# Power.net
KiCad netlist of a schematic drawn in Altium Designer
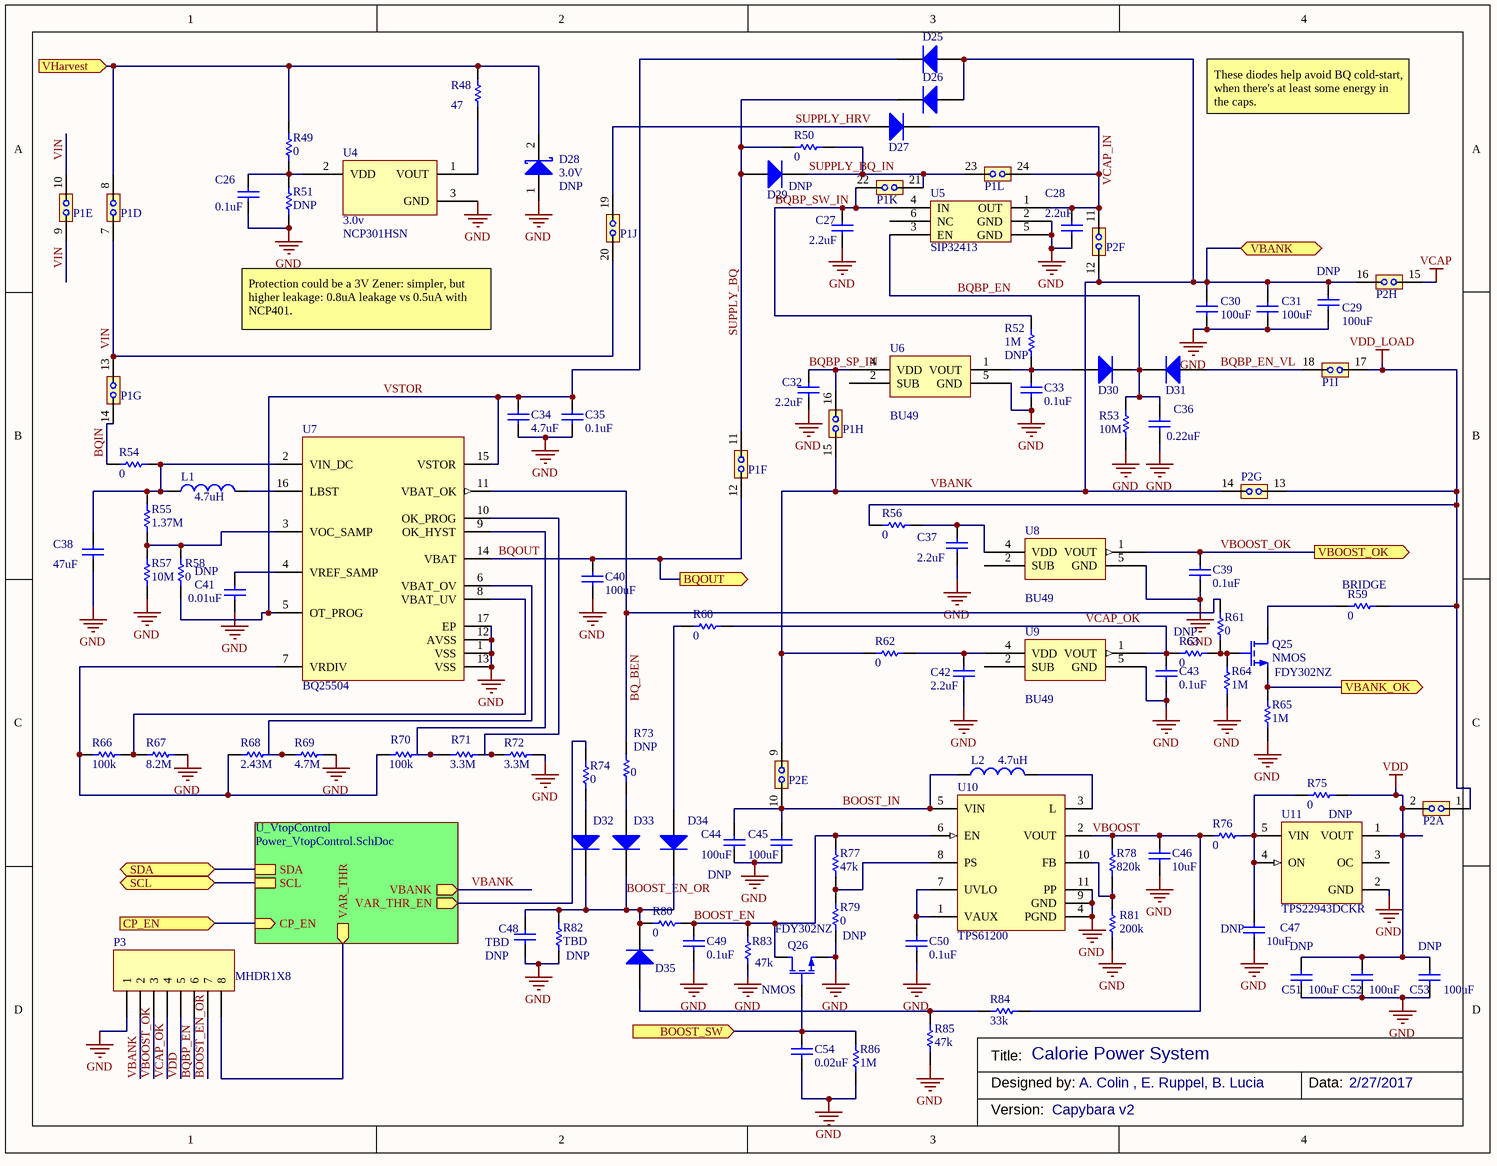
[diagram p0: Power.SchDoc]

(export (version "E")
  (design (tool "Eeschema 10.0.6"))
  (components
    (comp (ref "C26")
      (value "0.1uF")
      (footprint "0603")
      (description "Ceramic Capacitor (Surface Mount)")
      (fields
        (field (name "MANUFACTURER") "Murata Electronics North America")
        (field (name "MANUFACTURER PART NUMBER") "GRM188R71C104KA01D")
      )
      (libsource (lib "DRP_Basic_2014") (part "Cap"))
    )
    (comp (ref "C27")
      (value "2.2uF")
      (footprint "0603")
      (description "Ceramic Capacitor (Surface Mount)")
      (fields
        (field (name "MANUFACTURER") "Murata Electronics North America")
        (field (name "MANUFACTURER PART NUMBER") "GRM188R61C225KE15D")
      )
      (libsource (lib "DRP_Basic_2014") (part "Cap"))
    )
    (comp (ref "C28")
      (value "2.2uF")
      (footprint "0603")
      (description "Ceramic Capacitor (Surface Mount)")
      (fields
        (field (name "MANUFACTURER") "Murata Electronics North America")
        (field (name "MANUFACTURER PART NUMBER") "GRM188R61C225KE15D")
      )
      (libsource (lib "DRP_Basic_2014") (part "Cap"))
    )
    (comp (ref "C29")
      (value "100uF")
      (footprint "0805")
      (description "Ceramic Capacitor (Surface Mount)")
      (fields
        (field (name "MANUFACTURER") "Murata Electronics North America")
        (field (name "MANUFACTURER PART NUMBER") "GRM21BR60J107ME15L")
        (field (name "NOTE") "DNP")
      )
      (libsource (lib "DRP_Basic_2014") (part "Cap"))
    )
    (comp (ref "C30")
      (value "100uF")
      (footprint "0805")
      (description "Ceramic Capacitor (Surface Mount)")
      (fields
        (field (name "MANUFACTURER") "Murata Electronics North America")
        (field (name "MANUFACTURER PART NUMBER") "GRM21BR60G107ME15L")
      )
      (libsource (lib "DRP_Basic_2014") (part "Cap"))
    )
    (comp (ref "C31")
      (value "100uF")
      (footprint "0805")
      (description "Ceramic Capacitor (Surface Mount)")
      (fields
        (field (name "MANUFACTURER") "Murata Electronics North America")
        (field (name "MANUFACTURER PART NUMBER") "GRM21BR60G107ME15L")
      )
      (libsource (lib "DRP_Basic_2014") (part "Cap"))
    )
    (comp (ref "C32")
      (value "2.2uF")
      (footprint "0603")
      (description "Ceramic Capacitor (Surface Mount)")
      (fields
        (field (name "MANUFACTURER") "Murata Electronics North America")
        (field (name "MANUFACTURER PART NUMBER") "GRM188R61C225KE15D")
      )
      (libsource (lib "DRP_Basic_2014") (part "Cap"))
    )
    (comp (ref "C33")
      (value "0.1uF")
      (footprint "0603")
      (description "Ceramic Capacitor (Surface Mount)")
      (fields
        (field (name "MANUFACTURER") "Murata Electronics North America")
        (field (name "MANUFACTURER PART NUMBER") "GRM188R71C104KA01D")
      )
      (libsource (lib "DRP_Basic_2014") (part "Cap"))
    )
    (comp (ref "C34")
      (value "4.7uF")
      (footprint "0603")
      (description "Ceramic Capacitor (Surface Mount)")
      (fields
        (field (name "MANUFACTURER") "Samsung Electro-Mechanics")
        (field (name "MANUFACTURER PART NUMBER") "CL10B475KQ8NQNC")
      )
      (libsource (lib "DRP_Basic_2014") (part "Cap"))
    )
    (comp (ref "C35")
      (value "0.1uF")
      (footprint "0603")
      (description "Ceramic Capacitor (Surface Mount)")
      (fields
        (field (name "MANUFACTURER") "Murata Electronics North America")
        (field (name "MANUFACTURER PART NUMBER") "GRM188R71C104KA01D")
      )
      (libsource (lib "DRP_Basic_2014") (part "Cap"))
    )
    (comp (ref "C36")
      (value "0.22uF")
      (footprint "0603")
      (description "Ceramic Capacitor (Surface Mount)")
      (fields
        (field (name "MANUFACTURER") "Murata Electronics North America")
        (field (name "MANUFACTURER PART NUMBER") "GRM188R71E224KA88D")
      )
      (libsource (lib "DRP_Basic_2014") (part "Cap"))
    )
    (comp (ref "C37")
      (value "2.2uF")
      (footprint "0603")
      (description "Ceramic Capacitor (Surface Mount)")
      (fields
        (field (name "MANUFACTURER") "Murata Electronics North America")
        (field (name "MANUFACTURER PART NUMBER") "GRM188R61C225KE15D")
      )
      (libsource (lib "DRP_Basic_2014") (part "Cap"))
    )
    (comp (ref "C38")
      (value "47uF")
      (footprint "0603")
      (description "Ceramic Capacitor (Surface Mount)")
      (fields
        (field (name "MANUFACTURER") "Samsung Electro-Mechanics")
        (field (name "MANUFACTURER PART NUMBER") "CL10A476MR8NZNE")
      )
      (libsource (lib "DRP_Basic_2014") (part "Cap"))
    )
    (comp (ref "C39")
      (value "0.1uF")
      (footprint "0603")
      (description "Ceramic Capacitor (Surface Mount)")
      (fields
        (field (name "MANUFACTURER") "Murata Electronics North America")
        (field (name "MANUFACTURER PART NUMBER") "GRM188R71C104KA01D")
      )
      (libsource (lib "DRP_Basic_2014") (part "Cap"))
    )
    (comp (ref "C40")
      (value "100uF")
      (footprint "0805")
      (description "Ceramic Capacitor (Surface Mount)")
      (fields
        (field (name "MANUFACTURER") "Murata Electronics North America")
        (field (name "MANUFACTURER PART NUMBER") "GRM21BR60G107ME15L")
      )
      (libsource (lib "DRP_Basic_2014") (part "Cap"))
    )
    (comp (ref "C41")
      (value "0.01uF")
      (footprint "0603")
      (description "Ceramic Capacitor (Surface Mount)")
      (fields
        (field (name "MANUFACTURER") "Murata Electronics North America")
        (field (name "MANUFACTURER PART NUMBER") "GRM155R71E103JA01J")
      )
      (libsource (lib "DRP_Basic_2014") (part "Cap"))
    )
    (comp (ref "C42")
      (value "2.2uF")
      (footprint "0603")
      (description "Ceramic Capacitor (Surface Mount)")
      (fields
        (field (name "MANUFACTURER") "Murata Electronics North America")
        (field (name "MANUFACTURER PART NUMBER") "GRM188R61C225KE15D")
      )
      (libsource (lib "DRP_Basic_2014") (part "Cap"))
    )
    (comp (ref "C43")
      (value "0.1uF")
      (footprint "0603")
      (description "Ceramic Capacitor (Surface Mount)")
      (fields
        (field (name "MANUFACTURER") "Murata Electronics North America")
        (field (name "MANUFACTURER PART NUMBER") "GRM188R71C104KA01D")
      )
      (libsource (lib "DRP_Basic_2014") (part "Cap"))
    )
    (comp (ref "C44")
      (value "100uF")
      (footprint "0805")
      (description "Ceramic Capacitor (Surface Mount)")
      (fields
        (field (name "MANUFACTURER") "Murata Electronics North America")
        (field (name "MANUFACTURER PART NUMBER") "GRM21BR60G107ME15L")
        (field (name "NOTE") "DNP")
      )
      (libsource (lib "DRP_Basic_2014") (part "Cap"))
    )
    (comp (ref "C45")
      (value "100uF")
      (footprint "0805")
      (description "Ceramic Capacitor (Surface Mount)")
      (fields
        (field (name "MANUFACTURER") "Murata Electronics North America")
        (field (name "MANUFACTURER PART NUMBER") "GRM21BR60G107ME15L")
      )
      (libsource (lib "DRP_Basic_2014") (part "Cap"))
    )
    (comp (ref "C46")
      (value "10uF")
      (footprint "0603")
      (description "Ceramic Capacitor (Surface Mount)")
      (fields
        (field (name "MANUFACTURER") "Murata Electronics North America")
        (field (name "MANUFACTURER PART NUMBER") "GRM188R60J106ME47D")
      )
      (libsource (lib "DRP_Basic_2014") (part "Cap"))
    )
    (comp (ref "C47")
      (value "10uF")
      (footprint "0805")
      (description "Ceramic Capacitor (Surface Mount)")
      (fields
        (field (name "MANUFACTURER") "Murata Electronics North America")
        (field (name "MANUFACTURER PART NUMBER") "GRM21BR61E106MA73L")
        (field (name "NOTE") "DNP")
      )
      (libsource (lib "DRP_Basic_2014") (part "Cap"))
    )
    (comp (ref "C48")
      (value "TBD")
      (footprint "0603")
      (description "Ceramic Capacitor (Surface Mount)")
      (fields
        (field (name "MANUFACTURER") "Generic Ceramic Chip Cap (TBD)")
        (field (name "NOTE") "DNP")
        (field (name "Comment") "Cap")
      )
      (libsource (lib "DRP_Basic_2014") (part "Cap"))
    )
    (comp (ref "C49")
      (value "0.1uF")
      (footprint "0603")
      (description "Ceramic Capacitor (Surface Mount)")
      (fields
        (field (name "MANUFACTURER") "Murata Electronics North America")
        (field (name "MANUFACTURER PART NUMBER") "GRM188R71C104KA01D")
      )
      (libsource (lib "DRP_Basic_2014") (part "Cap"))
    )
    (comp (ref "C50")
      (value "0.1uF")
      (footprint "0603")
      (description "Ceramic Capacitor (Surface Mount)")
      (fields
        (field (name "MANUFACTURER") "Murata Electronics North America")
        (field (name "MANUFACTURER PART NUMBER") "GRM188R71C104KA01D")
      )
      (libsource (lib "DRP_Basic_2014") (part "Cap"))
    )
    (comp (ref "C51")
      (value "100uF")
      (footprint "0805")
      (description "Ceramic Capacitor (Surface Mount)")
      (fields
        (field (name "MANUFACTURER") "Murata Electronics North America")
        (field (name "MANUFACTURER PART NUMBER") "GRM21BR60G107ME15L")
        (field (name "NOTE") "DNP")
      )
      (libsource (lib "DRP_Basic_2014") (part "Cap"))
    )
    (comp (ref "C52")
      (value "100uF")
      (footprint "0805")
      (description "Ceramic Capacitor (Surface Mount)")
      (fields
        (field (name "MANUFACTURER") "Murata Electronics North America")
        (field (name "MANUFACTURER PART NUMBER") "GRM21BR60G107ME15L")
      )
      (libsource (lib "DRP_Basic_2014") (part "Cap"))
    )
    (comp (ref "C53")
      (value "100uF")
      (footprint "0805")
      (description "Ceramic Capacitor (Surface Mount)")
      (fields
        (field (name "MANUFACTURER") "Murata Electronics North America")
        (field (name "MANUFACTURER PART NUMBER") "GRM21BR60G107ME15L")
        (field (name "NOTE") "DNP")
      )
      (libsource (lib "DRP_Basic_2014") (part "Cap"))
    )
    (comp (ref "C54")
      (value "0.02uF")
      (footprint "0603")
      (description "Ceramic Capacitor (Surface Mount)")
      (fields
        (field (name "MANUFACTURER") "Samsung Electro-Mechanics")
        (field (name "MANUFACTURER PART NUMBER") "CL10B203KB8NNNC")
      )
      (libsource (lib "DRP_Basic_2014") (part "Cap"))
    )
    (comp (ref "D25")
      (value "Diode")
      (footprint "SOD-523")
      (description "General Purpose Diode")
      (fields
        (field (name "MANUFACTURER") "Vishay Semiconductor")
        (field (name "MANUFACTURER PART NUMBER") "BAS40-02V-V-G-08")
      )
      (libsource (lib "DRP_Basic_2014") (part "Diode"))
    )
    (comp (ref "D26")
      (value "Diode")
      (footprint "SOD-523")
      (description "General Purpose Diode")
      (fields
        (field (name "MANUFACTURER") "Vishay Semiconductor")
        (field (name "MANUFACTURER PART NUMBER") "BAS40-02V-V-G-08")
      )
      (libsource (lib "DRP_Basic_2014") (part "Diode"))
    )
    (comp (ref "D27")
      (value "Diode")
      (footprint "SOD-523")
      (description "General Purpose Diode")
      (fields
        (field (name "MANUFACTURER") "Vishay Semiconductor")
        (field (name "MANUFACTURER PART NUMBER") "BAS40-02V-V-G-08")
      )
      (libsource (lib "DRP_Basic_2014") (part "Diode"))
    )
    (comp (ref "D28")
      (value "3.0V")
      (footprint "DIOD-SOD-123-2_V")
      (fields
        (field (name "MANUFACTURER PART NUMBER") "MMSZ4683-TP")
        (field (name "MANUFACTURER") "Micro Commercial Co")
        (field (name "NOTE") "DNP")
        (field (name "DIGI-KEY PART NUMBER") "MMSZ4683-TPMSCT-ND")
      )
      (libsource (lib "Altium Content Vault") (part "CMP-0303-00003-1"))
    )
    (comp (ref "D29")
      (value "Diode")
      (footprint "SOD-523")
      (description "General Purpose Diode")
      (fields
        (field (name "MANUFACTURER") "Vishay Semiconductor")
        (field (name "MANUFACTURER PART NUMBER") "BAS40-02V-V-G-08")
        (field (name "NOTE") "DNP")
      )
      (libsource (lib "DRP_Basic_2014") (part "Diode"))
    )
    (comp (ref "D30")
      (value "Diode")
      (footprint "SOD-523")
      (description "General Purpose Diode")
      (fields
        (field (name "MANUFACTURER") "Vishay Semiconductor")
        (field (name "MANUFACTURER PART NUMBER") "BAS40-02V-V-G-08")
      )
      (libsource (lib "DRP_Basic_2014") (part "Diode"))
    )
    (comp (ref "D31")
      (value "Diode")
      (footprint "SOD-523")
      (description "General Purpose Diode")
      (fields
        (field (name "MANUFACTURER") "Vishay Semiconductor")
        (field (name "MANUFACTURER PART NUMBER") "BAS40-02V-V-G-08")
      )
      (libsource (lib "DRP_Basic_2014") (part "Diode"))
    )
    (comp (ref "D32")
      (value "Diode")
      (footprint "SOD-523")
      (description "General Purpose Diode")
      (fields
        (field (name "MANUFACTURER") "Vishay Semiconductor")
        (field (name "MANUFACTURER PART NUMBER") "BAS40-02V-V-G-08")
      )
      (libsource (lib "DRP_Basic_2014") (part "Diode"))
    )
    (comp (ref "D33")
      (value "Diode")
      (footprint "SOD-523")
      (description "General Purpose Diode")
      (fields
        (field (name "MANUFACTURER") "Vishay Semiconductor")
        (field (name "MANUFACTURER PART NUMBER") "BAS40-02V-V-G-08")
      )
      (libsource (lib "DRP_Basic_2014") (part "Diode"))
    )
    (comp (ref "D34")
      (value "Diode")
      (footprint "SOD-523")
      (description "General Purpose Diode")
      (fields
        (field (name "MANUFACTURER") "Vishay Semiconductor")
        (field (name "MANUFACTURER PART NUMBER") "BAS40-02V-V-G-08")
      )
      (libsource (lib "DRP_Basic_2014") (part "Diode"))
    )
    (comp (ref "D35")
      (value "Diode")
      (footprint "SOD-523")
      (description "General Purpose Diode")
      (fields
        (field (name "MANUFACTURER") "Vishay Semiconductor")
        (field (name "MANUFACTURER PART NUMBER") "BAS40-02V-V-G-08")
      )
      (libsource (lib "DRP_Basic_2014") (part "Diode"))
    )
    (comp (ref "L1")
      (value "4.7uH")
      (footprint "PFL1609")
      (description "Inductor")
      (fields
        (field (name "DISTRIBUTOR PART NUMBER") "994-PFL1609-472MEU")
        (field (name "MANUFACTURER") "Coilcraft")
      )
      (libsource (lib "Miscellaneous Devices") (part "Inductor"))
    )
    (comp (ref "L2")
      (value "4.7uH")
      (footprint "PFL1609")
      (description "Inductor")
      (fields
        (field (name "DISTRIBUTOR PART NUMBER") "994-PFL1609-472MEU")
        (field (name "MANUFACTURER") "Coilcraft")
      )
      (libsource (lib "Miscellaneous Devices") (part "Inductor"))
    )
    (comp (ref "P1") (value "JMPHDR_12") (footprint "MHDR2X12") (libsource (lib "") (part "JMPHDR_12_4")))
    (comp (ref "P2")
      (value "JMPHDR_8")
      (fields
        (field (name "DIGI-KEY PART NUMBER") "S9015E-08-ND")
        (field (name "MANUFACTURER") "Sullins Connector Solutions")
        (field (name "MANUFACTURER PART NUMBER") "GRPB082VWVN-RC")
      )
      (libsource (lib "") (part "JMPHDR_8_3"))
    )
    (comp (ref "P3")
      (value "MHDR1X8")
      (footprint "MHDR1X8")
      (description "Header, 8-Pin")
      (fields
        (field (name "DIGI-KEY PART NUMBER") "952-3361-ND")
        (field (name "DISTRIBUTOR PART NUMBER") "855-M52-5000845")
        (field (name "PUBLISHER") "Altium Limited")
      )
      (libsource (lib "Miscellaneous Connectors") (part "MHDR1X8"))
    )
    (comp (ref "Q25")
      (value "NMOS")
      (footprint "SOT-523-3")
      (description "N-Channel MOSFET")
      (fields
        (field (name "MANUFACTURER PART NUMBER") "FDY302NZ")
        (field (name "MANUFACTURER") "Fairchild")
        (field (name "DISTRIBUTOR PART NUMBER") "FDY302NZCT-ND")
      )
      (libsource (lib "DRP_Basic_2014") (part "MOSFET-N"))
    )
    (comp (ref "Q26")
      (value "NMOS")
      (footprint "SOT-523-3")
      (description "N-Channel MOSFET")
      (fields
        (field (name "MANUFACTURER PART NUMBER") "FDY302NZ")
        (field (name "MANUFACTURER") "Fairchild")
        (field (name "DISTRIBUTOR PART NUMBER") "FDY302NZCT-ND")
      )
      (libsource (lib "DRP_Basic_2014") (part "MOSFET-N"))
    )
    (comp (ref "R48")
      (value "47")
      (footprint "0603")
      (description "Chip Resistor (Surface Mount)")
      (fields
        (field (name "MANUFACTURER") "Yageo")
        (field (name "MANUFACTURER PART NUMBER") "RC0603JR-0747RL")
      )
      (libsource (lib "DRP_Basic_2014") (part "Res"))
    )
    (comp (ref "R49")
      (value "0")
      (footprint "0603")
      (description "Chip Resistor (Surface Mount)")
      (fields
        (field (name "MANUFACTURER") "Yageo")
        (field (name "MANUFACTURER PART NUMBER") "RC0603JR-070RL")
      )
      (libsource (lib "DRP_Basic_2014") (part "Res"))
    )
    (comp (ref "R50")
      (value "0")
      (footprint "0603")
      (description "Chip Resistor (Surface Mount)")
      (fields
        (field (name "MANUFACTURER") "Yageo")
        (field (name "MANUFACTURER PART NUMBER") "RC0603JR-070RL")
      )
      (libsource (lib "DRP_Basic_2014") (part "Res"))
    )
    (comp (ref "R51")
      (value "DNP")
      (footprint "0603")
      (description "Chip Resistor (Surface Mount)")
      (fields (field (name "MANUFACTURER") "Yageo") (field (name "Comment") "Res"))
      (libsource (lib "DRP_Basic_2014") (part "Res"))
    )
    (comp (ref "R52")
      (value "1M")
      (footprint "0603")
      (description "Chip Resistor (Surface Mount)")
      (fields
        (field (name "MANUFACTURER") "Yageo")
        (field (name "MANUFACTURER PART NUMBER") "RC0603FR-071ML")
        (field (name "NOTE") "DNP")
      )
      (libsource (lib "DRP_Basic_2014") (part "Res"))
    )
    (comp (ref "R53")
      (value "10M")
      (footprint "0603")
      (description "Chip Resistor (Surface Mount)")
      (fields
        (field (name "MANUFACTURER") "Yageo")
        (field (name "MANUFACTURER PART NUMBER") "RC0603JR-0710ML")
      )
      (libsource (lib "DRP_Basic_2014") (part "Res"))
    )
    (comp (ref "R54")
      (value "0")
      (footprint "0603")
      (description "Chip Resistor (Surface Mount)")
      (fields
        (field (name "MANUFACTURER") "Yageo")
        (field (name "MANUFACTURER PART NUMBER") "RC0603JR-070RL")
      )
      (libsource (lib "DRP_Basic_2014") (part "Res"))
    )
    (comp (ref "R55")
      (value "1.37M")
      (footprint "0603")
      (description "Chip Resistor (Surface Mount)")
      (fields
        (field (name "MANUFACTURER") "Vishay Dale")
        (field (name "MANUFACTURER PART NUMBER") "CRCW04021M37FKED")
      )
      (libsource (lib "DRP_Basic_2014") (part "Res"))
    )
    (comp (ref "R56")
      (value "0")
      (footprint "0603")
      (description "Chip Resistor (Surface Mount)")
      (fields
        (field (name "MANUFACTURER") "Yageo")
        (field (name "MANUFACTURER PART NUMBER") "RC0603JR-070RL")
      )
      (libsource (lib "DRP_Basic_2014") (part "Res"))
    )
    (comp (ref "R57")
      (value "10M")
      (footprint "0603")
      (description "Chip Resistor (Surface Mount)")
      (fields
        (field (name "MANUFACTURER") "Yageo")
        (field (name "MANUFACTURER PART NUMBER") "RC0603JR-0710ML")
      )
      (libsource (lib "DRP_Basic_2014") (part "Res"))
    )
    (comp (ref "R58")
      (value "0")
      (footprint "0603")
      (description "Chip Resistor (Surface Mount)")
      (fields
        (field (name "MANUFACTURER") "Yageo")
        (field (name "MANUFACTURER PART NUMBER") "RC0603JR-070RL")
        (field (name "NOTE") "DNP")
      )
      (libsource (lib "DRP_Basic_2014") (part "Res"))
    )
    (comp (ref "R59")
      (value "0")
      (footprint "0603")
      (description "Chip Resistor (Surface Mount)")
      (fields
        (field (name "MANUFACTURER") "Yageo")
        (field (name "MANUFACTURER PART NUMBER") "RC0603JR-070RL")
        (field (name "NOTE") "BRIDGE")
      )
      (libsource (lib "DRP_Basic_2014") (part "Res"))
    )
    (comp (ref "R60")
      (value "0")
      (footprint "0603")
      (description "Chip Resistor (Surface Mount)")
      (fields
        (field (name "MANUFACTURER") "Yageo")
        (field (name "MANUFACTURER PART NUMBER") "RC0603JR-070RL")
      )
      (libsource (lib "DRP_Basic_2014") (part "Res"))
    )
    (comp (ref "R61")
      (value "0")
      (footprint "0603")
      (description "Chip Resistor (Surface Mount)")
      (fields
        (field (name "MANUFACTURER") "Yageo")
        (field (name "MANUFACTURER PART NUMBER") "RC0603JR-070RL")
      )
      (libsource (lib "DRP_Basic_2014") (part "Res"))
    )
    (comp (ref "R62")
      (value "0")
      (footprint "0603")
      (description "Chip Resistor (Surface Mount)")
      (fields
        (field (name "MANUFACTURER") "Yageo")
        (field (name "MANUFACTURER PART NUMBER") "RC0603JR-070RL")
      )
      (libsource (lib "DRP_Basic_2014") (part "Res"))
    )
    (comp (ref "R63")
      (value "0")
      (footprint "0603")
      (description "Chip Resistor (Surface Mount)")
      (fields
        (field (name "MANUFACTURER") "Yageo")
        (field (name "MANUFACTURER PART NUMBER") "RC0603JR-070RL")
        (field (name "NOTE") "DNP")
      )
      (libsource (lib "DRP_Basic_2014") (part "Res"))
    )
    (comp (ref "R64")
      (value "1M")
      (footprint "0603")
      (description "Chip Resistor (Surface Mount)")
      (fields
        (field (name "MANUFACTURER") "Yageo")
        (field (name "MANUFACTURER PART NUMBER") "RC0603FR-071ML")
      )
      (libsource (lib "DRP_Basic_2014") (part "Res"))
    )
    (comp (ref "R65")
      (value "1M")
      (footprint "0603")
      (description "Chip Resistor (Surface Mount)")
      (fields
        (field (name "MANUFACTURER") "Yageo")
        (field (name "MANUFACTURER PART NUMBER") "RC0603FR-071ML")
      )
      (libsource (lib "DRP_Basic_2014") (part "Res"))
    )
    (comp (ref "R66")
      (value "100k")
      (footprint "0603")
      (description "Chip Resistor (Surface Mount)")
      (fields
        (field (name "MANUFACTURER") "Yageo")
        (field (name "MANUFACTURER PART NUMBER") "RT0603FRE07100KL")
      )
      (libsource (lib "DRP_Basic_2014") (part "Res"))
    )
    (comp (ref "R67")
      (value "8.2M")
      (footprint "0603")
      (description "Chip Resistor (Surface Mount)")
      (fields
        (field (name "MANUFACTURER") "Vishay Dale")
        (field (name "MANUFACTURER PART NUMBER") "CRCW06038M20FKEA")
      )
      (libsource (lib "DRP_Basic_2014") (part "Res"))
    )
    (comp (ref "R68")
      (value "2.43M")
      (footprint "0603")
      (description "Chip Resistor (Surface Mount)")
      (fields
        (field (name "MANUFACTURER") "Vishay")
        (field (name "MANUFACTURER PART NUMBER") "CRCW06032M43FKEA")
      )
      (libsource (lib "DRP_Basic_2014") (part "Res"))
    )
    (comp (ref "R69")
      (value "4.7M")
      (footprint "0603")
      (description "Chip Resistor (Surface Mount)")
      (fields
        (field (name "MANUFACTURER") "Generic Chip Res (TBD)")
        (field (name "MANUFACTURER PART NUMBER") "RC0603FR-074M7L")
      )
      (libsource (lib "DRP_Basic_2014") (part "Res"))
    )
    (comp (ref "R70")
      (value "100k")
      (footprint "0603")
      (description "Chip Resistor (Surface Mount)")
      (fields
        (field (name "MANUFACTURER") "Yageo")
        (field (name "MANUFACTURER PART NUMBER") "RC0603FR-071M6L")
      )
      (libsource (lib "DRP_Basic_2014") (part "Res"))
    )
    (comp (ref "R71")
      (value "3.3M")
      (footprint "0603")
      (description "Chip Resistor (Surface Mount)")
      (fields
        (field (name "MANUFACTURER") "Yageo")
        (field (name "MANUFACTURER PART NUMBER") "RC0603FR-071M6L")
      )
      (libsource (lib "DRP_Basic_2014") (part "Res"))
    )
    (comp (ref "R72")
      (value "3.3M")
      (footprint "0603")
      (description "Chip Resistor (Surface Mount)")
      (fields
        (field (name "MANUFACTURER") "Vishay Dale")
        (field (name "MANUFACTURER PART NUMBER") "CRCW06033M30FKEA")
      )
      (libsource (lib "DRP_Basic_2014") (part "Res"))
    )
    (comp (ref "R73")
      (value "0")
      (footprint "0603")
      (description "Chip Resistor (Surface Mount)")
      (fields
        (field (name "MANUFACTURER") "Yageo")
        (field (name "MANUFACTURER PART NUMBER") "RC0603JR-070RL")
        (field (name "NOTE") "DNP")
      )
      (libsource (lib "DRP_Basic_2014") (part "Res"))
    )
    (comp (ref "R74")
      (value "0")
      (footprint "0603")
      (description "Chip Resistor (Surface Mount)")
      (fields
        (field (name "MANUFACTURER") "Yageo")
        (field (name "MANUFACTURER PART NUMBER") "RC0603JR-070RL")
      )
      (libsource (lib "DRP_Basic_2014") (part "Res"))
    )
    (comp (ref "R75")
      (value "0")
      (footprint "0603")
      (description "Chip Resistor (Surface Mount)")
      (fields
        (field (name "MANUFACTURER") "Yageo")
        (field (name "MANUFACTURER PART NUMBER") "RC0603JR-070RL")
      )
      (libsource (lib "DRP_Basic_2014") (part "Res"))
    )
    (comp (ref "R76")
      (value "0")
      (footprint "0603")
      (description "Chip Resistor (Surface Mount)")
      (fields
        (field (name "MANUFACTURER") "Yageo")
        (field (name "MANUFACTURER PART NUMBER") "RC0603JR-070RL")
      )
      (libsource (lib "DRP_Basic_2014") (part "Res"))
    )
    (comp (ref "R77")
      (value "47k")
      (footprint "0603")
      (description "Chip Resistor (Surface Mount)")
      (fields
        (field (name "MANUFACTURER") "Yageo")
        (field (name "MANUFACTURER PART NUMBER") "RT0603DRD0747KL")
      )
      (libsource (lib "DRP_Basic_2014") (part "Res"))
    )
    (comp (ref "R78")
      (value "820k")
      (footprint "0603")
      (description "Chip Resistor (Surface Mount)")
      (fields
        (field (name "MANUFACTURER") "Yageo")
        (field (name "MANUFACTURER PART NUMBER") "RC0603FR-07820KL")
      )
      (libsource (lib "DRP_Basic_2014") (part "Res"))
    )
    (comp (ref "R79")
      (value "0")
      (footprint "0603")
      (description "Chip Resistor (Surface Mount)")
      (fields
        (field (name "MANUFACTURER") "Yageo")
        (field (name "MANUFACTURER PART NUMBER") "RC0603JR-070RL")
        (field (name "NOTE") "DNP")
      )
      (libsource (lib "DRP_Basic_2014") (part "Res"))
    )
    (comp (ref "R80")
      (value "0")
      (footprint "0603")
      (description "Chip Resistor (Surface Mount)")
      (fields
        (field (name "MANUFACTURER") "Yageo")
        (field (name "MANUFACTURER PART NUMBER") "RC0603JR-070RL")
      )
      (libsource (lib "DRP_Basic_2014") (part "Res"))
    )
    (comp (ref "R81")
      (value "200k")
      (footprint "0603")
      (description "Chip Resistor (Surface Mount)")
      (fields
        (field (name "MANUFACTURER") "Yageo")
        (field (name "MANUFACTURER PART NUMBER") "RC0603FR-07200KL")
      )
      (libsource (lib "DRP_Basic_2014") (part "Res"))
    )
    (comp (ref "R82")
      (value "TBD")
      (footprint "0603")
      (description "Chip Resistor (Surface Mount)")
      (fields
        (field (name "MANUFACTURER") "Generic Chip Res (TBD)")
        (field (name "NOTE") "DNP")
        (field (name "Comment") "Res")
      )
      (libsource (lib "DRP_Basic_2014") (part "Res"))
    )
    (comp (ref "R83")
      (value "47k")
      (footprint "0603")
      (description "Chip Resistor (Surface Mount)")
      (fields
        (field (name "MANUFACTURER") "Yageo")
        (field (name "MANUFACTURER PART NUMBER") "RT0603DRD0747KL")
      )
      (libsource (lib "DRP_Basic_2014") (part "Res"))
    )
    (comp (ref "R84")
      (value "33k")
      (footprint "0603")
      (description "Chip Resistor (Surface Mount)")
      (fields
        (field (name "MANUFACTURER") "Yageo")
        (field (name "MANUFACTURER PART NUMBER") "RT0603DRE0733KL")
      )
      (libsource (lib "DRP_Basic_2014") (part "Res"))
    )
    (comp (ref "R85")
      (value "47k")
      (footprint "0603")
      (description "Chip Resistor (Surface Mount)")
      (fields
        (field (name "MANUFACTURER") "Yageo")
        (field (name "MANUFACTURER PART NUMBER") "RT0603DRD0747KL")
      )
      (libsource (lib "DRP_Basic_2014") (part "Res"))
    )
    (comp (ref "R86")
      (value "1M")
      (footprint "0603")
      (description "Chip Resistor (Surface Mount)")
      (fields
        (field (name "MANUFACTURER") "Yageo")
        (field (name "MANUFACTURER PART NUMBER") "RC0603JR-0710ML")
      )
      (libsource (lib "DRP_Basic_2014") (part "Res"))
    )
    (comp (ref "U4")
      (value "3.0v")
      (footprint "SOT23-5")
      (description "IC DETECTOR OPEN-DRAIN")
      (fields
        (field (name "NAME") "NCP301HSN")
        (field (name "DIGI-KEY PART NUMBER") "NCP301HSN30T1GOSCT-ND")
        (field (name "DISTRIBUTOR PART NUMBER") "863-NCP301HSN30T1G")
      )
      (libsource (lib "Sprite") (part "NCP301"))
    )
    (comp (ref "U5")
      (value "SIP32413")
      (footprint "SC70-6")
      (fields
        (field (name "DIGI-KEY PART NUMBER") "SIP32431DR3-T1GE3CT-ND")
        (field (name "DISTRIBUTOR PART NUMBER") "781-SIP32431DR3-GE3")
        (field (name "MANUFACTURER") "Vishay Semiconductors")
      )
      (libsource (lib "Sprite") (part "SIP32431"))
    )
    (comp (ref "U6")
      (value "BU48")
      (footprint "SOP4")
      (description "IC DETECTOR OPEN-DRAIN")
      (fields
        (field (name "NAME") "BU49")
        (field (name "DIGI-KEY PART NUMBER") "BU4917F-TR-ND")
        (field (name "DISTRIBUTOR PART NUMBER") "BU4917F-TR")
      )
      (libsource (lib "Sprite") (part "BU48"))
    )
    (comp (ref "U7")
      (value "BQ25504")
      (footprint "VQFN-16")
      (fields
        (field (name "DIGI-KEY PART NUMBER") "296-29741-1-ND")
        (field (name "DISTRIBUTOR PART NUMBER") "595-BQ25504RGTR")
        (field (name "MANUFACTURER") "BQ25504RGTT")
      )
      (libsource (lib "Sprite") (part "BQ25504"))
    )
    (comp (ref "U8")
      (value "BU49")
      (footprint "SOP4")
      (description "IC DETECTOR CMOS")
      (fields
        (field (name "NAME") "BU49")
        (field (name "DIGI-KEY PART NUMBER") "BU4924F-TR-ND")
        (field (name "DISTRIBUTOR PART NUMBER") "BU4924F-TR")
      )
      (libsource (lib "Sprite") (part "BU49"))
    )
    (comp (ref "U9")
      (value "BU49")
      (footprint "SOP4")
      (description "IC DETECTOR CMOS")
      (fields
        (field (name "NAME") "BU49")
        (field (name "DIGI-KEY PART NUMBER") "BU4924F-TR-ND")
        (field (name "DISTRIBUTOR PART NUMBER") "BU4924F-TR")
      )
      (libsource (lib "Sprite") (part "BU49"))
    )
    (comp (ref "U10")
      (value "TPS61200")
      (footprint "VSON-10")
      (fields
        (field (name "MANUFACTURER") "Texas Instruments")
        (field (name "MANUFACTURER PART NUMBER") "TPS61200DRCR")
        (field (name "DISTRIBUTOR PART NUMBER") "296-27017-1-ND")
      )
      (libsource (lib "Sprite") (part "TPS61200"))
    )
    (comp (ref "U11")
      (value "TPS22943DCKR")
      (footprint "SC70-5")
      (fields
        (field (name "MANUFACTURER") "Texas Instruments")
        (field (name "DISTRIBUTOR PART NUMBER") "296-25316-1-ND")
        (field (name "NOTE") "DNP")
        (field (name "MOUSER PART NUMBER") "595-TPS22943DCKR")
      )
      (libsource (lib "altium-import") (part "root_0_TI-TPS22943DCK5_"))
    )
  )
  (nets
    (net (code "1") (name "/BOOST_EN") (class "Default")
      (node (ref "C49") (pin "2") (pinfunction "2_2") (pintype "passive"))
      (node (ref "Q26") (pin "3") (pinfunction "D_3") (pintype "passive"))
      (node (ref "R77") (pin "2") (pinfunction "2_2") (pintype "passive"))
      (node (ref "R80") (pin "2") (pinfunction "2_2") (pintype "passive"))
      (node (ref "R83") (pin "2") (pinfunction "2_2") (pintype "passive"))
      (node (ref "U10") (pin "6") (pinfunction "EN_6") (pintype "input"))
    )
    (net (code "2") (name "/BOOST_EN_OR") (class "Default")
      (node (ref "C48") (pin "1") (pinfunction "1_1") (pintype "passive"))
      (node (ref "D32") (pin "2") (pinfunction "C_2") (pintype "passive"))
      (node (ref "D33") (pin "2") (pinfunction "C_2") (pintype "passive"))
      (node (ref "D34") (pin "2") (pinfunction "C_2") (pintype "passive"))
      (node (ref "D35") (pin "2") (pinfunction "C_2") (pintype "passive"))
      (node (ref "P3") (pin "7") (pinfunction "7_7") (pintype "passive"))
      (node (ref "R80") (pin "1") (pinfunction "1_1") (pintype "passive"))
      (node (ref "R82") (pin "2") (pinfunction "2_2") (pintype "passive"))
    )
    (net (code "3") (name "/BOOST_IN") (class "Default")
      (node (ref "C44") (pin "2") (pinfunction "2_2") (pintype "passive"))
      (node (ref "C45") (pin "2") (pinfunction "2_2") (pintype "passive"))
      (node (ref "L2") (pin "1") (pinfunction "1_1") (pintype "passive"))
      (node (ref "P2") (pin "10") (pinfunction "10_10") (pintype "passive"))
      (node (ref "U10") (pin "5") (pinfunction "VIN_5") (pintype "power_in"))
    )
    (net (code "4") (name "/BOOST_SW") (class "Default")
      (node (ref "C54") (pin "2") (pinfunction "2_2") (pintype "passive"))
      (node (ref "Q26") (pin "1") (pinfunction "G_1") (pintype "passive"))
      (node (ref "R86") (pin "2") (pinfunction "2_2") (pintype "passive"))
    )
    (net (code "5") (name "/BQBP_EN") (class "Default")
      (node (ref "C36") (pin "2") (pinfunction "2_2") (pintype "passive"))
      (node (ref "D30") (pin "2") (pinfunction "C_2") (pintype "passive"))
      (node (ref "D31") (pin "2") (pinfunction "C_2") (pintype "passive"))
      (node (ref "P3") (pin "6") (pinfunction "6_6") (pintype "passive"))
      (node (ref "R53") (pin "2") (pinfunction "2_2") (pintype "passive"))
      (node (ref "U5") (pin "3") (pinfunction "EN_3") (pintype "passive"))
    )
    (net (code "6") (name "/BQBP_EN_VL") (class "Default")
      (node (ref "D31") (pin "1") (pinfunction "A_1") (pintype "passive"))
      (node (ref "P1") (pin "18") (pinfunction "18_18") (pintype "passive"))
    )
    (net (code "7") (name "/BQBP_SP_IN") (class "Default")
      (node (ref "C32") (pin "2") (pinfunction "2_2") (pintype "passive"))
      (node (ref "P1") (pin "16") (pinfunction "16_16") (pintype "passive"))
      (node (ref "U6") (pin "4") (pinfunction "VDD_4") (pintype "power_in"))
    )
    (net (code "8") (name "/BQBP_SW_IN") (class "Default")
      (node (ref "C27") (pin "2") (pinfunction "2_2") (pintype "passive"))
      (node (ref "P1") (pin "22") (pinfunction "22_22") (pintype "passive"))
      (node (ref "R52") (pin "2") (pinfunction "2_2") (pintype "passive"))
      (node (ref "U5") (pin "4") (pinfunction "IN_4") (pintype "passive"))
    )
    (net (code "9") (name "/BQIN") (class "Default")
      (node (ref "P1") (pin "14") (pinfunction "14_14") (pintype "passive"))
      (node (ref "R54") (pin "1") (pinfunction "1_1") (pintype "passive"))
    )
    (net (code "10") (name "/BQOUT") (class "Default")
      (node (ref "C40") (pin "2") (pinfunction "2_2") (pintype "passive"))
      (node (ref "P1") (pin "12") (pinfunction "12_12") (pintype "passive"))
      (node (ref "U7") (pin "14") (pinfunction "VBAT_14") (pintype "power_in"))
    )
    (net (code "11") (name "/BQ_BEN") (class "Default")
      (node (ref "R61") (pin "2") (pinfunction "2_2") (pintype "passive"))
      (node (ref "R73") (pin "2") (pinfunction "2_2") (pintype "passive"))
      (node (ref "U7") (pin "11") (pinfunction "VBAT_OK_11") (pintype "output"))
    )
    (net (code "15") (name "/SUPPLY_BQ") (class "Default")
      (node (ref "D26") (pin "2") (pinfunction "C_2") (pintype "passive"))
      (node (ref "D29") (pin "1") (pinfunction "A_1") (pintype "passive"))
      (node (ref "P1") (pin "11") (pinfunction "11_11") (pintype "passive"))
      (node (ref "R50") (pin "1") (pinfunction "1_1") (pintype "passive"))
    )
    (net (code "16") (name "/SUPPLY_BQ_IN") (class "Default")
      (node (ref "D29") (pin "2") (pinfunction "C_2") (pintype "passive"))
      (node (ref "P1") (pin "21") (pinfunction "21_21") (pintype "passive"))
      (node (ref "P1") (pin "23") (pinfunction "23_23") (pintype "passive"))
      (node (ref "R50") (pin "2") (pinfunction "2_2") (pintype "passive"))
    )
    (net (code "17") (name "/SUPPLY_HRV") (class "Default")
      (node (ref "D27") (pin "1") (pinfunction "A_1") (pintype "passive"))
      (node (ref "P1") (pin "19") (pinfunction "19_19") (pintype "passive"))
    )
    (net (code "18") (name "/VAR_THR") (class "Default")
      (node (ref "P3") (pin "8") (pinfunction "8_8") (pintype "passive"))
    )
    (net (code "19") (name "/VAR_THR_EN") (class "Default")
      (node (ref "R74") (pin "2") (pinfunction "2_2") (pintype "passive"))
    )
    (net (code "20") (name "/VBANK") (class "Default")
      (node (ref "C29") (pin "2") (pinfunction "2_2") (pintype "passive"))
      (node (ref "C30") (pin "2") (pinfunction "2_2") (pintype "passive"))
      (node (ref "C31") (pin "2") (pinfunction "2_2") (pintype "passive"))
      (node (ref "D25") (pin "1") (pinfunction "A_1") (pintype "passive"))
      (node (ref "D26") (pin "1") (pinfunction "A_1") (pintype "passive"))
      (node (ref "P1") (pin "15") (pinfunction "15_15") (pintype "passive"))
      (node (ref "P2") (pin "12") (pinfunction "12_12") (pintype "passive"))
      (node (ref "P2") (pin "14") (pinfunction "14_14") (pintype "passive"))
      (node (ref "P2") (pin "16") (pinfunction "16_16") (pintype "passive"))
      (node (ref "P2") (pin "9") (pinfunction "9_9") (pintype "passive"))
      (node (ref "P3") (pin "2") (pinfunction "2_2") (pintype "passive"))
      (node (ref "R62") (pin "1") (pinfunction "1_1") (pintype "passive"))
    )
    (net (code "21") (name "/VBANK_OK") (class "Default")
      (node (ref "Q25") (pin "2") (pinfunction "S_2") (pintype "passive"))
      (node (ref "R65") (pin "2") (pinfunction "2_2") (pintype "passive"))
    )
    (net (code "22") (name "/VBOOST") (class "Default")
      (node (ref "C46") (pin "2") (pinfunction "2_2") (pintype "passive"))
      (node (ref "R76") (pin "1") (pinfunction "1_1") (pintype "passive"))
      (node (ref "R78") (pin "2") (pinfunction "2_2") (pintype "passive"))
      (node (ref "R84") (pin "2") (pinfunction "2_2") (pintype "passive"))
      (node (ref "U10") (pin "2") (pinfunction "VOUT_2") (pintype "passive"))
    )
    (net (code "23") (name "/VBOOST_OK") (class "Default")
      (node (ref "C39") (pin "2") (pinfunction "2_2") (pintype "passive"))
      (node (ref "P3") (pin "3") (pinfunction "3_3") (pintype "passive"))
      (node (ref "U8") (pin "1") (pinfunction "VOUT_1") (pintype "output"))
    )
    (net (code "24") (name "/VCAP_IN") (class "Default")
      (node (ref "C28") (pin "2") (pinfunction "2_2") (pintype "passive"))
      (node (ref "D27") (pin "2") (pinfunction "C_2") (pintype "passive"))
      (node (ref "P1") (pin "24") (pinfunction "24_24") (pintype "passive"))
      (node (ref "P2") (pin "11") (pinfunction "11_11") (pintype "passive"))
      (node (ref "U5") (pin "1") (pinfunction "OUT_1") (pintype "passive"))
    )
    (net (code "25") (name "/VCAP_OK") (class "Default")
      (node (ref "C43") (pin "2") (pinfunction "2_2") (pintype "passive"))
      (node (ref "P3") (pin "4") (pinfunction "4_4") (pintype "passive"))
      (node (ref "R60") (pin "2") (pinfunction "2_2") (pintype "passive"))
      (node (ref "R63") (pin "1") (pinfunction "1_1") (pintype "passive"))
      (node (ref "U9") (pin "1") (pinfunction "VOUT_1") (pintype "output"))
    )
    (net (code "26") (name "/VHarvest") (class "Default")
      (node (ref "D28") (pin "2") (pinfunction "K_2") (pintype "passive"))
      (node (ref "P1") (pin "8") (pinfunction "8_8") (pintype "passive"))
      (node (ref "R48") (pin "1") (pinfunction "1_1") (pintype "passive"))
      (node (ref "R49") (pin "2") (pinfunction "2_2") (pintype "passive"))
    )
    (net (code "27") (name "/VIN") (class "Default")
      (node (ref "P1") (pin "10") (pinfunction "10_10") (pintype "passive"))
      (node (ref "P1") (pin "13") (pinfunction "13_13") (pintype "passive"))
      (node (ref "P1") (pin "20") (pinfunction "20_20") (pintype "passive"))
      (node (ref "P1") (pin "7") (pinfunction "7_7") (pintype "passive"))
      (node (ref "P1") (pin "9") (pinfunction "9_9") (pintype "passive"))
    )
    (net (code "28") (name "/VSTOR") (class "Default")
      (node (ref "C34") (pin "2") (pinfunction "2_2") (pintype "passive"))
      (node (ref "C35") (pin "2") (pinfunction "2_2") (pintype "passive"))
      (node (ref "D25") (pin "2") (pinfunction "C_2") (pintype "passive"))
      (node (ref "R58") (pin "1") (pinfunction "1_1") (pintype "passive"))
      (node (ref "U7") (pin "15") (pinfunction "VSTOR_15") (pintype "passive"))
      (node (ref "U7") (pin "5") (pinfunction "OT_PROG_5") (pintype "passive"))
    )
    (net (code "29") (name "GND") (class "Default")
      (node (ref "C26") (pin "1") (pinfunction "1_1") (pintype "passive"))
      (node (ref "C27") (pin "1") (pinfunction "1_1") (pintype "passive"))
      (node (ref "C28") (pin "1") (pinfunction "1_1") (pintype "passive"))
      (node (ref "C29") (pin "1") (pinfunction "1_1") (pintype "passive"))
      (node (ref "C30") (pin "1") (pinfunction "1_1") (pintype "passive"))
      (node (ref "C31") (pin "1") (pinfunction "1_1") (pintype "passive"))
      (node (ref "C32") (pin "1") (pinfunction "1_1") (pintype "passive"))
      (node (ref "C33") (pin "1") (pinfunction "1_1") (pintype "passive"))
      (node (ref "C34") (pin "1") (pinfunction "1_1") (pintype "passive"))
      (node (ref "C35") (pin "1") (pinfunction "1_1") (pintype "passive"))
      (node (ref "C36") (pin "1") (pinfunction "1_1") (pintype "passive"))
      (node (ref "C37") (pin "1") (pinfunction "1_1") (pintype "passive"))
      (node (ref "C38") (pin "2") (pinfunction "2_2") (pintype "passive"))
      (node (ref "C39") (pin "1") (pinfunction "1_1") (pintype "passive"))
      (node (ref "C40") (pin "1") (pinfunction "1_1") (pintype "passive"))
      (node (ref "C41") (pin "1") (pinfunction "1_1") (pintype "passive"))
      (node (ref "C42") (pin "1") (pinfunction "1_1") (pintype "passive"))
      (node (ref "C43") (pin "1") (pinfunction "1_1") (pintype "passive"))
      (node (ref "C44") (pin "1") (pinfunction "1_1") (pintype "passive"))
      (node (ref "C45") (pin "1") (pinfunction "1_1") (pintype "passive"))
      (node (ref "C46") (pin "1") (pinfunction "1_1") (pintype "passive"))
      (node (ref "C47") (pin "1") (pinfunction "1_1") (pintype "passive"))
      (node (ref "C48") (pin "2") (pinfunction "2_2") (pintype "passive"))
      (node (ref "C49") (pin "1") (pinfunction "1_1") (pintype "passive"))
      (node (ref "C50") (pin "1") (pinfunction "1_1") (pintype "passive"))
      (node (ref "C51") (pin "1") (pinfunction "1_1") (pintype "passive"))
      (node (ref "C52") (pin "1") (pinfunction "1_1") (pintype "passive"))
      (node (ref "C53") (pin "1") (pinfunction "1_1") (pintype "passive"))
      (node (ref "C54") (pin "1") (pinfunction "1_1") (pintype "passive"))
      (node (ref "D28") (pin "1") (pinfunction "A_1") (pintype "passive"))
      (node (ref "P3") (pin "1") (pinfunction "1_1") (pintype "passive"))
      (node (ref "Q26") (pin "2") (pinfunction "S_2") (pintype "passive"))
      (node (ref "R51") (pin "1") (pinfunction "1_1") (pintype "passive"))
      (node (ref "R53") (pin "1") (pinfunction "1_1") (pintype "passive"))
      (node (ref "R57") (pin "1") (pinfunction "1_1") (pintype "passive"))
      (node (ref "R64") (pin "1") (pinfunction "1_1") (pintype "passive"))
      (node (ref "R65") (pin "1") (pinfunction "1_1") (pintype "passive"))
      (node (ref "R67") (pin "2") (pinfunction "2_2") (pintype "passive"))
      (node (ref "R69") (pin "2") (pinfunction "2_2") (pintype "passive"))
      (node (ref "R72") (pin "2") (pinfunction "2_2") (pintype "passive"))
      (node (ref "R79") (pin "1") (pinfunction "1_1") (pintype "passive"))
      (node (ref "R81") (pin "1") (pinfunction "1_1") (pintype "passive"))
      (node (ref "R82") (pin "1") (pinfunction "1_1") (pintype "passive"))
      (node (ref "R83") (pin "1") (pinfunction "1_1") (pintype "passive"))
      (node (ref "R85") (pin "1") (pinfunction "1_1") (pintype "passive"))
      (node (ref "R86") (pin "1") (pinfunction "1_1") (pintype "passive"))
      (node (ref "U10") (pin "11") (pinfunction "PP_11") (pintype "power_in"))
      (node (ref "U10") (pin "4") (pinfunction "PGND_4") (pintype "power_in"))
      (node (ref "U10") (pin "9") (pinfunction "GND_9") (pintype "power_in"))
      (node (ref "U11") (pin "2") (pinfunction "GND_2") (pintype "power_in"))
      (node (ref "U4") (pin "3") (pinfunction "GND_3") (pintype "power_in"))
      (node (ref "U5") (pin "2") (pinfunction "GND_2") (pintype "passive"))
      (node (ref "U5") (pin "5") (pinfunction "GND_5") (pintype "passive"))
      (node (ref "U6") (pin "5") (pinfunction "GND_5") (pintype "power_in"))
      (node (ref "U7") (pin "1") (pinfunction "VSS_1") (pintype "power_in"))
      (node (ref "U7") (pin "12") (pinfunction "AVSS_12") (pintype "power_in"))
      (node (ref "U7") (pin "13") (pinfunction "VSS_13") (pintype "power_in"))
      (node (ref "U7") (pin "17") (pinfunction "EP_17") (pintype "power_in"))
      (node (ref "U8") (pin "5") (pinfunction "GND_5") (pintype "power_in"))
      (node (ref "U9") (pin "5") (pinfunction "GND_5") (pintype "power_in"))
    )
    (net (code "30") (name "Net-(D30-A)") (class "Default")
      (node (ref "C33") (pin "2") (pinfunction "2_2") (pintype "passive"))
      (node (ref "D30") (pin "1") (pinfunction "A_1") (pintype "passive"))
      (node (ref "R52") (pin "1") (pinfunction "1_1") (pintype "passive"))
      (node (ref "U6") (pin "1") (pinfunction "VOUT_1") (pintype "open_collector"))
    )
    (net (code "31") (name "Net-(D32-A)") (class "Default")
      (node (ref "D32") (pin "1") (pinfunction "A_1") (pintype "passive"))
      (node (ref "R74") (pin "1") (pinfunction "1_1") (pintype "passive"))
    )
    (net (code "32") (name "Net-(D33-A)") (class "Default")
      (node (ref "D33") (pin "1") (pinfunction "A_1") (pintype "passive"))
      (node (ref "R73") (pin "1") (pinfunction "1_1") (pintype "passive"))
    )
    (net (code "33") (name "Net-(D34-A)") (class "Default")
      (node (ref "D34") (pin "1") (pinfunction "A_1") (pintype "passive"))
      (node (ref "R60") (pin "1") (pinfunction "1_1") (pintype "passive"))
    )
    (net (code "34") (name "Net-(D35-A)") (class "Default")
      (node (ref "D35") (pin "1") (pinfunction "A_1") (pintype "passive"))
      (node (ref "R84") (pin "1") (pinfunction "1_1") (pintype "passive"))
      (node (ref "R85") (pin "2") (pinfunction "2_2") (pintype "passive"))
    )
    (net (code "35") (name "Net-(Q25-D)") (class "Default")
      (node (ref "Q25") (pin "3") (pinfunction "D_3") (pintype "passive"))
      (node (ref "R59") (pin "1") (pinfunction "1_1") (pintype "passive"))
    )
    (net (code "36") (name "Net-(Q25-G)") (class "Default")
      (node (ref "Q25") (pin "1") (pinfunction "G_1") (pintype "passive"))
      (node (ref "R61") (pin "1") (pinfunction "1_1") (pintype "passive"))
      (node (ref "R63") (pin "2") (pinfunction "2_2") (pintype "passive"))
      (node (ref "R64") (pin "2") (pinfunction "2_2") (pintype "passive"))
    )
    (net (code "37") (name "Net-(U4-VDD)") (class "Default")
      (node (ref "C26") (pin "2") (pinfunction "2_2") (pintype "passive"))
      (node (ref "R49") (pin "1") (pinfunction "1_1") (pintype "passive"))
      (node (ref "R51") (pin "2") (pinfunction "2_2") (pintype "passive"))
      (node (ref "U4") (pin "2") (pinfunction "VDD_2") (pintype "power_in"))
    )
    (net (code "38") (name "Net-(U4-VOUT)") (class "Default")
      (node (ref "R48") (pin "2") (pinfunction "2_2") (pintype "passive"))
      (node (ref "U4") (pin "1") (pinfunction "VOUT_1") (pintype "open_collector"))
    )
    (net (code "39") (name "Net-(U7-LBST)") (class "Default")
      (node (ref "L1") (pin "2") (pinfunction "2_2") (pintype "passive"))
      (node (ref "U7") (pin "16") (pinfunction "LBST_16") (pintype "passive"))
    )
    (net (code "40") (name "Net-(U7-OK_HYST)") (class "Default")
      (node (ref "R70") (pin "2") (pinfunction "2_2") (pintype "passive"))
      (node (ref "R71") (pin "1") (pinfunction "1_1") (pintype "passive"))
      (node (ref "U7") (pin "9") (pinfunction "OK_HYST_9") (pintype "passive"))
    )
    (net (code "41") (name "Net-(U7-OK_PROG)") (class "Default")
      (node (ref "R71") (pin "2") (pinfunction "2_2") (pintype "passive"))
      (node (ref "R72") (pin "1") (pinfunction "1_1") (pintype "passive"))
      (node (ref "U7") (pin "10") (pinfunction "OK_PROG_10") (pintype "passive"))
    )
    (net (code "42") (name "Net-(U7-VBAT_OV)") (class "Default")
      (node (ref "R68") (pin "2") (pinfunction "2_2") (pintype "passive"))
      (node (ref "R69") (pin "1") (pinfunction "1_1") (pintype "passive"))
      (node (ref "U7") (pin "6") (pinfunction "VBAT_OV_6") (pintype "passive"))
    )
    (net (code "43") (name "Net-(U7-VBAT_UV)") (class "Default")
      (node (ref "R66") (pin "2") (pinfunction "2_2") (pintype "passive"))
      (node (ref "R67") (pin "1") (pinfunction "1_1") (pintype "passive"))
      (node (ref "U7") (pin "8") (pinfunction "VBAT_UV_8") (pintype "passive"))
    )
    (net (code "44") (name "Net-(U7-VIN_DC)") (class "Default")
      (node (ref "C38") (pin "1") (pinfunction "1_1") (pintype "passive"))
      (node (ref "L1") (pin "1") (pinfunction "1_1") (pintype "passive"))
      (node (ref "R54") (pin "2") (pinfunction "2_2") (pintype "passive"))
      (node (ref "R55") (pin "2") (pinfunction "2_2") (pintype "passive"))
      (node (ref "U7") (pin "2") (pinfunction "VIN_DC_2") (pintype "power_in"))
    )
    (net (code "45") (name "Net-(U7-VOC_SAMP)") (class "Default")
      (node (ref "R55") (pin "1") (pinfunction "1_1") (pintype "passive"))
      (node (ref "R57") (pin "2") (pinfunction "2_2") (pintype "passive"))
      (node (ref "R58") (pin "2") (pinfunction "2_2") (pintype "passive"))
      (node (ref "U7") (pin "3") (pinfunction "VOC_SAMP_3") (pintype "passive"))
    )
    (net (code "46") (name "Net-(U7-VRDIV)") (class "Default")
      (node (ref "R66") (pin "1") (pinfunction "1_1") (pintype "passive"))
      (node (ref "R68") (pin "1") (pinfunction "1_1") (pintype "passive"))
      (node (ref "R70") (pin "1") (pinfunction "1_1") (pintype "passive"))
      (node (ref "U7") (pin "7") (pinfunction "VRDIV_7") (pintype "passive"))
    )
    (net (code "47") (name "Net-(U7-VREF_SAMP)") (class "Default")
      (node (ref "C41") (pin "2") (pinfunction "2_2") (pintype "passive"))
      (node (ref "U7") (pin "4") (pinfunction "VREF_SAMP_4") (pintype "passive"))
    )
    (net (code "48") (name "Net-(U8-VDD)") (class "Default")
      (node (ref "C37") (pin "2") (pinfunction "2_2") (pintype "passive"))
      (node (ref "R56") (pin "1") (pinfunction "1_1") (pintype "passive"))
      (node (ref "U8") (pin "4") (pinfunction "VDD_4") (pintype "power_in"))
    )
    (net (code "49") (name "Net-(U9-VDD)") (class "Default")
      (node (ref "C42") (pin "2") (pinfunction "2_2") (pintype "passive"))
      (node (ref "R62") (pin "2") (pinfunction "2_2") (pintype "passive"))
      (node (ref "U9") (pin "4") (pinfunction "VDD_4") (pintype "power_in"))
    )
    (net (code "50") (name "Net-(U10-FB)") (class "Default")
      (node (ref "R78") (pin "1") (pinfunction "1_1") (pintype "passive"))
      (node (ref "R81") (pin "2") (pinfunction "2_2") (pintype "passive"))
      (node (ref "U10") (pin "10") (pinfunction "FB_10") (pintype "passive"))
    )
    (net (code "51") (name "Net-(U10-L)") (class "Default")
      (node (ref "L2") (pin "2") (pinfunction "2_2") (pintype "passive"))
      (node (ref "U10") (pin "3") (pinfunction "L_3") (pintype "passive"))
    )
    (net (code "52") (name "Net-(U10-PS)") (class "Default")
      (node (ref "R77") (pin "1") (pinfunction "1_1") (pintype "passive"))
      (node (ref "R79") (pin "2") (pinfunction "2_2") (pintype "passive"))
      (node (ref "U10") (pin "8") (pinfunction "PS_8") (pintype "passive"))
    )
    (net (code "53") (name "Net-(U10-UVLO)") (class "Default")
      (node (ref "C50") (pin "2") (pinfunction "2_2") (pintype "passive"))
      (node (ref "U10") (pin "1") (pinfunction "VAUX_1") (pintype "passive"))
      (node (ref "U10") (pin "7") (pinfunction "UVLO_7") (pintype "passive"))
    )
    (net (code "54") (name "Net-(U11-ON)") (class "Default")
      (node (ref "C47") (pin "2") (pinfunction "2_2") (pintype "passive"))
      (node (ref "R75") (pin "1") (pinfunction "1_1") (pintype "passive"))
      (node (ref "R76") (pin "2") (pinfunction "2_2") (pintype "passive"))
      (node (ref "U11") (pin "4") (pinfunction "ON_4") (pintype "input"))
      (node (ref "U11") (pin "5") (pinfunction "VIN_5") (pintype "power_in"))
    )
    (net (code "55") (name "VCAP") (class "Default")
      (node (ref "P2") (pin "15") (pinfunction "15_15") (pintype "passive"))
    )
    (net (code "56") (name "VDD") (class "Default")
      (node (ref "C51") (pin "2") (pinfunction "2_2") (pintype "passive"))
      (node (ref "C52") (pin "2") (pinfunction "2_2") (pintype "passive"))
      (node (ref "C53") (pin "2") (pinfunction "2_2") (pintype "passive"))
      (node (ref "P2") (pin "2") (pinfunction "2_2") (pintype "passive"))
      (node (ref "P3") (pin "5") (pinfunction "5_5") (pintype "passive"))
      (node (ref "R75") (pin "2") (pinfunction "2_2") (pintype "passive"))
      (node (ref "U11") (pin "1") (pinfunction "VOUT_1") (pintype "power_in"))
    )
    (net (code "57") (name "VDD_LOAD") (class "Default")
      (node (ref "P1") (pin "17") (pinfunction "17_17") (pintype "passive"))
      (node (ref "P2") (pin "1") (pinfunction "1_1") (pintype "passive"))
      (node (ref "P2") (pin "13") (pinfunction "13_13") (pintype "passive"))
      (node (ref "R56") (pin "2") (pinfunction "2_2") (pintype "passive"))
      (node (ref "R59") (pin "2") (pinfunction "2_2") (pintype "passive"))
    )
    (net (code "58") (name "unconnected-(U5-NC-Pad6)") (class "Default")
      (node (ref "U5") (pin "6") (pinfunction "NC_6") (pintype "passive"))
    )
    (net (code "59") (name "unconnected-(U6-SUB-Pad2)") (class "Default")
      (node (ref "U6") (pin "2") (pinfunction "SUB_2") (pintype "passive"))
    )
    (net (code "60") (name "unconnected-(U8-SUB-Pad2)") (class "Default")
      (node (ref "U8") (pin "2") (pinfunction "SUB_2") (pintype "passive"))
    )
    (net (code "61") (name "unconnected-(U9-SUB-Pad2)") (class "Default")
      (node (ref "U9") (pin "2") (pinfunction "SUB_2") (pintype "passive"))
    )
    (net (code "62") (name "unconnected-(U11-OC-Pad3)") (class "Default")
      (node (ref "U11") (pin "3") (pinfunction "OC_3") (pintype "open_collector"))
    )
  )
)
